# chariotgauge.net
KiCad netlist of a schematic drawn in EAGLE
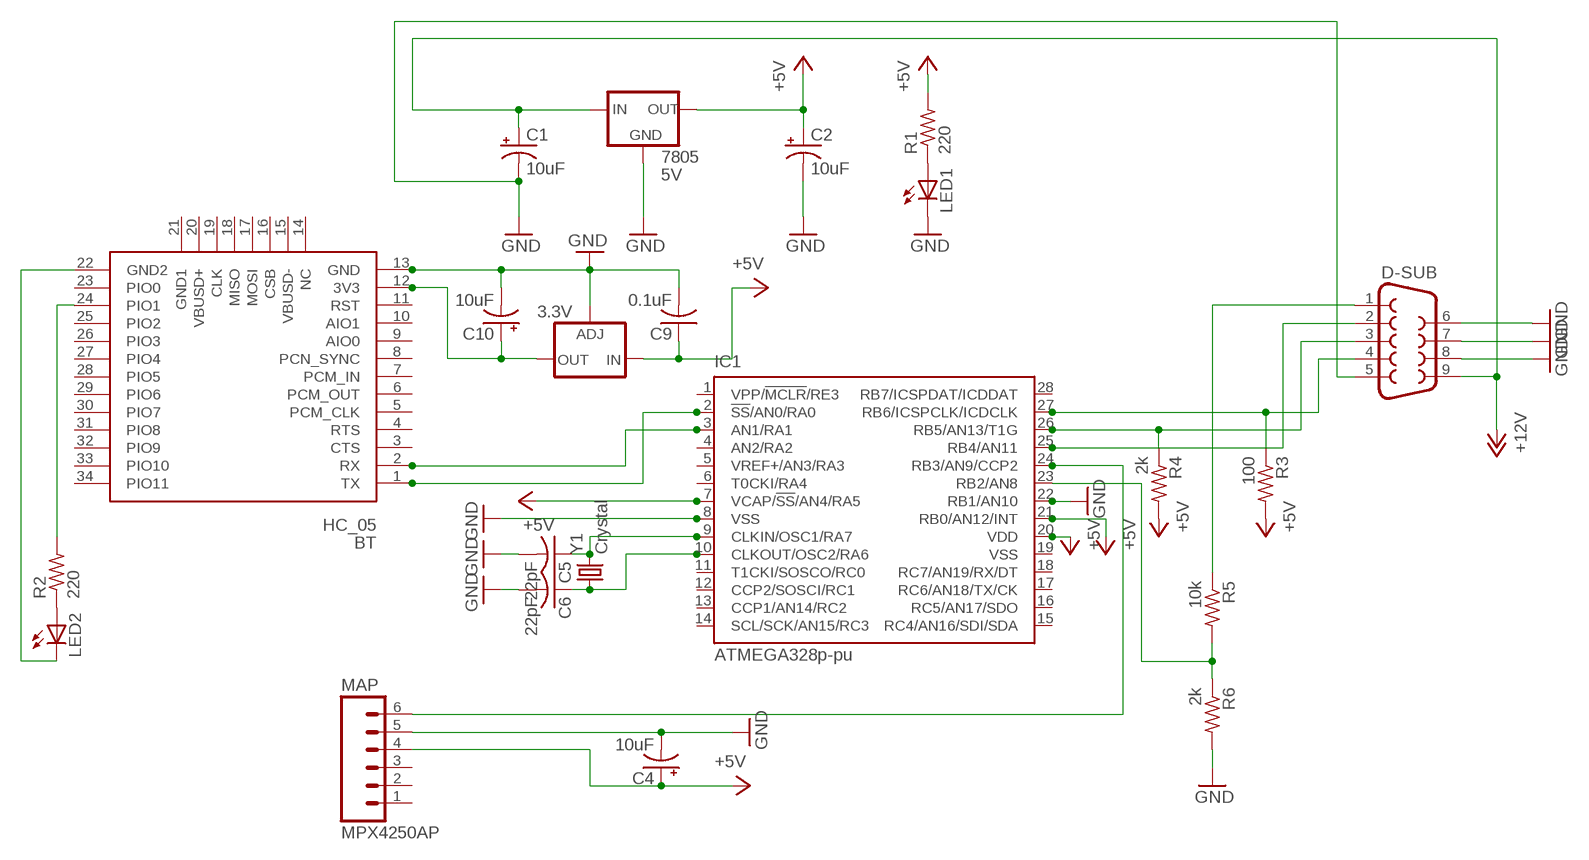
[diagram p0: schematic, sheet 1]

(export (version "E")
  (design (tool "Eeschema 10.0.6"))
  (components
    (comp (ref "3.3V")
      (value "LM317TL")
      (footprint "eagle-import:317TL")
      (libsource (lib "eagle-import") (part "LM317TL"))
    )
    (comp (ref "7805")
      (value "5V")
      (footprint "eagle-import:78XXL")
      (libsource (lib "eagle-import") (part "78XXL"))
    )
    (comp (ref "BT")
      (value "HC_05")
      (footprint "eagle-import:BLUETOOTH_SMD")
      (libsource (lib "eagle-import") (part "HC_05"))
    )
    (comp (ref "C1")
      (value "10uF")
      (footprint "eagle-import:CPOL-RADIAL-10UF-25V")
      (libsource (lib "eagle-import") (part "CAP_POLPTH2"))
    )
    (comp (ref "C2")
      (value "10uF")
      (footprint "eagle-import:CPOL-RADIAL-10UF-25V")
      (libsource (lib "eagle-import") (part "CAP_POLPTH2"))
    )
    (comp (ref "C4")
      (value "10uF")
      (footprint "eagle-import:CPOL-RADIAL-10UF-25V")
      (libsource (lib "eagle-import") (part "CAP_POLPTH2"))
    )
    (comp (ref "C5")
      (value "22pF")
      (footprint "eagle-import:C025-025X050")
      (libsource (lib "eagle-import") (part "C-US025-025X050"))
    )
    (comp (ref "C6")
      (value "22pF")
      (footprint "eagle-import:C025-025X050")
      (libsource (lib "eagle-import") (part "C-US025-025X050"))
    )
    (comp (ref "C9")
      (value "0.1uF")
      (footprint "eagle-import:C025-025X050")
      (libsource (lib "eagle-import") (part "C-US025-025X050"))
    )
    (comp (ref "C10")
      (value "10uF")
      (footprint "eagle-import:CPOL-RADIAL-10UF-25V")
      (libsource (lib "eagle-import") (part "CAP_POLPTH2"))
    )
    (comp (ref "D-SUB")
      (value "DB9FEMALE")
      (footprint "eagle-import:DB9")
      (libsource (lib "eagle-import") (part "DB9FEMALE"))
    )
    (comp (ref "IC1")
      (value "ATMEGA328p-pu")
      (footprint "eagle-import:DIL28-3")
      (libsource (lib "eagle-import") (part "PIC16F1516/18P"))
    )
    (comp (ref "LED1")
      (value "LED5MM")
      (footprint "eagle-import:LED5MM")
      (libsource (lib "eagle-import") (part "LED5MM"))
    )
    (comp (ref "LED2")
      (value "LED5MM")
      (footprint "eagle-import:LED5MM")
      (libsource (lib "eagle-import") (part "LED5MM"))
    )
    (comp (ref "MAP")
      (value "MPX4250AP")
      (footprint "eagle-import:1X06_LONGPADS")
      (libsource (lib "eagle-import") (part "M06LONGPADS"))
    )
    (comp (ref "R1")
      (value "220")
      (footprint "eagle-import:0204_7")
      (libsource (lib "eagle-import") (part "R-US_0204/7"))
    )
    (comp (ref "R2")
      (value "220")
      (footprint "eagle-import:0204_7")
      (libsource (lib "eagle-import") (part "R-US_0204/7"))
    )
    (comp (ref "R3")
      (value "100")
      (footprint "eagle-import:0204_7")
      (libsource (lib "eagle-import") (part "R-US_0204/7"))
    )
    (comp (ref "R4")
      (value "2k")
      (footprint "eagle-import:0204_7")
      (libsource (lib "eagle-import") (part "R-US_0204/7"))
    )
    (comp (ref "R5")
      (value "10k")
      (footprint "eagle-import:0204_7")
      (libsource (lib "eagle-import") (part "R-US_0204/7"))
    )
    (comp (ref "R6")
      (value "2k")
      (footprint "eagle-import:0204_7")
      (libsource (lib "eagle-import") (part "R-US_0204/7"))
    )
    (comp (ref "Y1")
      (value "Crystal")
      (footprint "eagle-import:HC49US")
      (libsource (lib "eagle-import") (part "CRYSTALHC49US"))
    )
  )
  (nets
    (net (code "1") (name "+5V") (class "Default")
      (node (ref "3.3V") (pin "3") (pinfunction "IN_3") (pintype "input"))
      (node (ref "7805") (pin "OUT") (pinfunction "OUT_OUT") (pintype "passive"))
      (node (ref "C2") (pin "1") (pinfunction "+_1") (pintype "passive"))
      (node (ref "C4") (pin "1") (pinfunction "+_1") (pintype "passive"))
      (node (ref "C9") (pin "1") (pinfunction "1_1") (pintype "passive"))
      (node (ref "IC1") (pin "20") (pinfunction "VDD_20") (pintype "power_in"))
      (node (ref "IC1") (pin "21") (pinfunction "RB0/AN12/INT_21") (pintype "bidirectional"))
      (node (ref "IC1") (pin "7") (pinfunction "VCAP/~{SS}/AN4/RA5_7") (pintype "bidirectional"))
      (node (ref "MAP") (pin "4") (pinfunction "4_4") (pintype "passive"))
      (node (ref "R1") (pin "2") (pinfunction "2_2") (pintype "passive"))
      (node (ref "R3") (pin "2") (pinfunction "2_2") (pintype "passive"))
      (node (ref "R4") (pin "2") (pinfunction "2_2") (pintype "passive"))
    )
    (net (code "2") (name "+12V") (class "Default")
      (node (ref "7805") (pin "IN") (pinfunction "IN_IN") (pintype "input"))
      (node (ref "C1") (pin "1") (pinfunction "+_1") (pintype "passive"))
      (node (ref "D-SUB") (pin "9") (pinfunction "9_9") (pintype "passive"))
    )
    (net (code "3") (name "/VSS") (class "Default")
      (node (ref "IC1") (pin "19") (pinfunction "VSS_19") (pintype "power_in"))
    )
    (net (code "4") (name "GND") (class "Default")
      (node (ref "3.3V") (pin "1") (pinfunction "ADJ_1") (pintype "input"))
      (node (ref "7805") (pin "GND") (pinfunction "GND_GND") (pintype "input"))
      (node (ref "BT") (pin "13") (pinfunction "GND_13") (pintype "bidirectional"))
      (node (ref "C1") (pin "2") (pinfunction "-_2") (pintype "passive"))
      (node (ref "C10") (pin "2") (pinfunction "-_2") (pintype "passive"))
      (node (ref "C2") (pin "2") (pinfunction "-_2") (pintype "passive"))
      (node (ref "C4") (pin "2") (pinfunction "-_2") (pintype "passive"))
      (node (ref "C5") (pin "2") (pinfunction "2_2") (pintype "passive"))
      (node (ref "C6") (pin "2") (pinfunction "2_2") (pintype "passive"))
      (node (ref "C9") (pin "2") (pinfunction "2_2") (pintype "passive"))
      (node (ref "D-SUB") (pin "5") (pinfunction "5_5") (pintype "passive"))
      (node (ref "D-SUB") (pin "6") (pinfunction "6_6") (pintype "passive"))
      (node (ref "D-SUB") (pin "7") (pinfunction "7_7") (pintype "passive"))
      (node (ref "D-SUB") (pin "8") (pinfunction "8_8") (pintype "passive"))
      (node (ref "IC1") (pin "22") (pinfunction "RB1/AN10_22") (pintype "bidirectional"))
      (node (ref "IC1") (pin "8") (pinfunction "VSS_8") (pintype "power_in"))
      (node (ref "LED1") (pin "K") (pinfunction "C_K") (pintype "passive"))
      (node (ref "MAP") (pin "5") (pinfunction "5_5") (pintype "passive"))
      (node (ref "R6") (pin "2") (pinfunction "2_2") (pintype "passive"))
    )
    (net (code "5") (name "Net-(3.3V-OUT)") (class "Default")
      (node (ref "3.3V") (pin "2") (pinfunction "OUT_2") (pintype "passive"))
      (node (ref "BT") (pin "12") (pinfunction "3V3_12") (pintype "bidirectional"))
      (node (ref "C10") (pin "1") (pinfunction "+_1") (pintype "passive"))
    )
    (net (code "6") (name "Net-(BT-GND2)") (class "Default")
      (node (ref "BT") (pin "22") (pinfunction "GND2_22") (pintype "bidirectional"))
      (node (ref "LED2") (pin "K") (pinfunction "C_K") (pintype "passive"))
    )
    (net (code "7") (name "Net-(BT-PIO1)") (class "Default")
      (node (ref "BT") (pin "24") (pinfunction "PIO1_24") (pintype "bidirectional"))
      (node (ref "R2") (pin "2") (pinfunction "2_2") (pintype "passive"))
    )
    (net (code "8") (name "Net-(BT-RX)") (class "Default")
      (node (ref "BT") (pin "2") (pinfunction "RX_2") (pintype "bidirectional"))
      (node (ref "IC1") (pin "3") (pinfunction "AN1/RA1_3") (pintype "bidirectional"))
    )
    (net (code "9") (name "Net-(BT-TX)") (class "Default")
      (node (ref "BT") (pin "1") (pinfunction "TX_1") (pintype "bidirectional"))
      (node (ref "IC1") (pin "2") (pinfunction "~{SS}/AN0/RA0_2") (pintype "bidirectional"))
    )
    (net (code "10") (name "Net-(D-SUB-Pad1)") (class "Default")
      (node (ref "D-SUB") (pin "1") (pinfunction "1_1") (pintype "passive"))
      (node (ref "R5") (pin "1") (pinfunction "1_1") (pintype "passive"))
    )
    (net (code "11") (name "Net-(IC1-CLKIN{slash}OSC1{slash}RA7)") (class "Default")
      (node (ref "C5") (pin "1") (pinfunction "1_1") (pintype "passive"))
      (node (ref "IC1") (pin "9") (pinfunction "CLKIN/OSC1/RA7_9") (pintype "bidirectional"))
      (node (ref "Y1") (pin "2") (pinfunction "2_2") (pintype "passive"))
    )
    (net (code "12") (name "Net-(IC1-CLKOUT{slash}OSC2{slash}RA6)") (class "Default")
      (node (ref "C6") (pin "1") (pinfunction "1_1") (pintype "passive"))
      (node (ref "IC1") (pin "10") (pinfunction "CLKOUT/OSC2/RA6_10") (pintype "bidirectional"))
      (node (ref "Y1") (pin "1") (pinfunction "1_1") (pintype "passive"))
    )
    (net (code "13") (name "Net-(IC1-RB2{slash}AN8)") (class "Default")
      (node (ref "IC1") (pin "23") (pinfunction "RB2/AN8_23") (pintype "bidirectional"))
      (node (ref "R5") (pin "2") (pinfunction "2_2") (pintype "passive"))
      (node (ref "R6") (pin "1") (pinfunction "1_1") (pintype "passive"))
    )
    (net (code "14") (name "Net-(IC1-RB3{slash}AN9{slash}CCP2)") (class "Default")
      (node (ref "IC1") (pin "24") (pinfunction "RB3/AN9/CCP2_24") (pintype "bidirectional"))
      (node (ref "MAP") (pin "6") (pinfunction "6_6") (pintype "passive"))
    )
    (net (code "15") (name "Net-(IC1-RB4{slash}AN11)") (class "Default")
      (node (ref "D-SUB") (pin "2") (pinfunction "2_2") (pintype "passive"))
      (node (ref "IC1") (pin "25") (pinfunction "RB4/AN11_25") (pintype "bidirectional"))
    )
    (net (code "16") (name "Net-(IC1-RB5{slash}AN13{slash}T1G)") (class "Default")
      (node (ref "D-SUB") (pin "3") (pinfunction "3_3") (pintype "passive"))
      (node (ref "IC1") (pin "26") (pinfunction "RB5/AN13/T1G_26") (pintype "bidirectional"))
      (node (ref "R4") (pin "1") (pinfunction "1_1") (pintype "passive"))
    )
    (net (code "17") (name "Net-(IC1-RB6{slash}ICSPCLK{slash}ICDCLK)") (class "Default")
      (node (ref "D-SUB") (pin "4") (pinfunction "4_4") (pintype "passive"))
      (node (ref "IC1") (pin "27") (pinfunction "RB6/ICSPCLK/ICDCLK_27") (pintype "bidirectional"))
      (node (ref "R3") (pin "1") (pinfunction "1_1") (pintype "passive"))
    )
    (net (code "18") (name "Net-(LED1-PadA)") (class "Default")
      (node (ref "LED1") (pin "A") (pinfunction "A_A") (pintype "passive"))
      (node (ref "R1") (pin "1") (pinfunction "1_1") (pintype "passive"))
    )
    (net (code "19") (name "Net-(LED2-PadA)") (class "Default")
      (node (ref "LED2") (pin "A") (pinfunction "A_A") (pintype "passive"))
      (node (ref "R2") (pin "1") (pinfunction "1_1") (pintype "passive"))
    )
    (net (code "20") (name "unconnected-(BT-AIO0-Pad9)") (class "Default")
      (node (ref "BT") (pin "9") (pinfunction "AIO0_9") (pintype "bidirectional"))
    )
    (net (code "21") (name "unconnected-(BT-AIO1-Pad10)") (class "Default")
      (node (ref "BT") (pin "10") (pinfunction "AIO1_10") (pintype "bidirectional"))
    )
    (net (code "22") (name "unconnected-(BT-CLK-Pad19)") (class "Default")
      (node (ref "BT") (pin "19") (pinfunction "CLK_19") (pintype "bidirectional"))
    )
    (net (code "23") (name "unconnected-(BT-CSB-Pad16)") (class "Default")
      (node (ref "BT") (pin "16") (pinfunction "CSB_16") (pintype "bidirectional"))
    )
    (net (code "24") (name "unconnected-(BT-CTS-Pad3)") (class "Default")
      (node (ref "BT") (pin "3") (pinfunction "CTS_3") (pintype "bidirectional"))
    )
    (net (code "25") (name "unconnected-(BT-GND1-Pad21)") (class "Default")
      (node (ref "BT") (pin "21") (pinfunction "GND1_21") (pintype "bidirectional"))
    )
    (net (code "26") (name "unconnected-(BT-MISO-Pad18)") (class "Default")
      (node (ref "BT") (pin "18") (pinfunction "MISO_18") (pintype "bidirectional"))
    )
    (net (code "27") (name "unconnected-(BT-MOSI-Pad17)") (class "Default")
      (node (ref "BT") (pin "17") (pinfunction "MOSI_17") (pintype "bidirectional"))
    )
    (net (code "28") (name "unconnected-(BT-NC-Pad14)") (class "Default")
      (node (ref "BT") (pin "14") (pinfunction "NC_14") (pintype "bidirectional"))
    )
    (net (code "29") (name "unconnected-(BT-PCM_CLK-Pad5)") (class "Default")
      (node (ref "BT") (pin "5") (pinfunction "PCM_CLK_5") (pintype "bidirectional"))
    )
    (net (code "30") (name "unconnected-(BT-PCM_IN-Pad7)") (class "Default")
      (node (ref "BT") (pin "7") (pinfunction "PCM_IN_7") (pintype "bidirectional"))
    )
    (net (code "31") (name "unconnected-(BT-PCM_OUT-Pad6)") (class "Default")
      (node (ref "BT") (pin "6") (pinfunction "PCM_OUT_6") (pintype "bidirectional"))
    )
    (net (code "32") (name "unconnected-(BT-PCN_SYNC-Pad8)") (class "Default")
      (node (ref "BT") (pin "8") (pinfunction "PCN_SYNC_8") (pintype "bidirectional"))
    )
    (net (code "33") (name "unconnected-(BT-PIO0-Pad23)") (class "Default")
      (node (ref "BT") (pin "23") (pinfunction "PIO0_23") (pintype "bidirectional"))
    )
    (net (code "34") (name "unconnected-(BT-PIO2-Pad25)") (class "Default")
      (node (ref "BT") (pin "25") (pinfunction "PIO2_25") (pintype "bidirectional"))
    )
    (net (code "35") (name "unconnected-(BT-PIO3-Pad26)") (class "Default")
      (node (ref "BT") (pin "26") (pinfunction "PIO3_26") (pintype "bidirectional"))
    )
    (net (code "36") (name "unconnected-(BT-PIO4-Pad27)") (class "Default")
      (node (ref "BT") (pin "27") (pinfunction "PIO4_27") (pintype "bidirectional"))
    )
    (net (code "37") (name "unconnected-(BT-PIO5-Pad28)") (class "Default")
      (node (ref "BT") (pin "28") (pinfunction "PIO5_28") (pintype "bidirectional"))
    )
    (net (code "38") (name "unconnected-(BT-PIO6-Pad29)") (class "Default")
      (node (ref "BT") (pin "29") (pinfunction "PIO6_29") (pintype "bidirectional"))
    )
    (net (code "39") (name "unconnected-(BT-PIO7-Pad30)") (class "Default")
      (node (ref "BT") (pin "30") (pinfunction "PIO7_30") (pintype "bidirectional"))
    )
    (net (code "40") (name "unconnected-(BT-PIO8-Pad31)") (class "Default")
      (node (ref "BT") (pin "31") (pinfunction "PIO8_31") (pintype "bidirectional"))
    )
    (net (code "41") (name "unconnected-(BT-PIO9-Pad32)") (class "Default")
      (node (ref "BT") (pin "32") (pinfunction "PIO9_32") (pintype "bidirectional"))
    )
    (net (code "42") (name "unconnected-(BT-PIO10-Pad33)") (class "Default")
      (node (ref "BT") (pin "33") (pinfunction "PIO10_33") (pintype "bidirectional"))
    )
    (net (code "43") (name "unconnected-(BT-PIO11-Pad34)") (class "Default")
      (node (ref "BT") (pin "34") (pinfunction "PIO11_34") (pintype "bidirectional"))
    )
    (net (code "44") (name "unconnected-(BT-RST-Pad11)") (class "Default")
      (node (ref "BT") (pin "11") (pinfunction "RST_11") (pintype "bidirectional"))
    )
    (net (code "45") (name "unconnected-(BT-RTS-Pad4)") (class "Default")
      (node (ref "BT") (pin "4") (pinfunction "RTS_4") (pintype "bidirectional"))
    )
    (net (code "46") (name "unconnected-(BT-VBUSD+-Pad20)") (class "Default")
      (node (ref "BT") (pin "20") (pinfunction "VBUSD+_20") (pintype "bidirectional"))
    )
    (net (code "47") (name "unconnected-(BT-VBUSD--Pad15)") (class "Default")
      (node (ref "BT") (pin "15") (pinfunction "VBUSD-_15") (pintype "bidirectional"))
    )
    (net (code "48") (name "unconnected-(IC1-AN2{slash}RA2-Pad4)") (class "Default")
      (node (ref "IC1") (pin "4") (pinfunction "AN2/RA2_4") (pintype "bidirectional"))
    )
    (net (code "49") (name "unconnected-(IC1-CCP1{slash}AN14{slash}RC2-Pad13)") (class "Default")
      (node (ref "IC1") (pin "13") (pinfunction "CCP1/AN14/RC2_13") (pintype "bidirectional"))
    )
    (net (code "50") (name "unconnected-(IC1-CCP2{slash}SOSCI{slash}RC1-Pad12)") (class "Default")
      (node (ref "IC1") (pin "12") (pinfunction "CCP2/SOSCI/RC1_12") (pintype "bidirectional"))
    )
    (net (code "51") (name "unconnected-(IC1-RB7{slash}ICSPDAT{slash}ICDDAT-Pad28)") (class "Default")
      (node (ref "IC1") (pin "28") (pinfunction "RB7/ICSPDAT/ICDDAT_28") (pintype "bidirectional"))
    )
    (net (code "52") (name "unconnected-(IC1-RC4{slash}AN16{slash}SDI{slash}SDA-Pad15)") (class "Default")
      (node (ref "IC1") (pin "15") (pinfunction "RC4/AN16/SDI/SDA_15") (pintype "bidirectional"))
    )
    (net (code "53") (name "unconnected-(IC1-RC5{slash}AN17{slash}SDO-Pad16)") (class "Default")
      (node (ref "IC1") (pin "16") (pinfunction "RC5/AN17/SDO_16") (pintype "bidirectional"))
    )
    (net (code "54") (name "unconnected-(IC1-RC6{slash}AN18{slash}TX{slash}CK-Pad17)") (class "Default")
      (node (ref "IC1") (pin "17") (pinfunction "RC6/AN18/TX/CK_17") (pintype "bidirectional"))
    )
    (net (code "55") (name "unconnected-(IC1-RC7{slash}AN19{slash}RX{slash}DT-Pad18)") (class "Default")
      (node (ref "IC1") (pin "18") (pinfunction "RC7/AN19/RX/DT_18") (pintype "bidirectional"))
    )
    (net (code "56") (name "unconnected-(IC1-SCL{slash}SCK{slash}AN15{slash}RC3-Pad14)") (class "Default")
      (node (ref "IC1") (pin "14") (pinfunction "SCL/SCK/AN15/RC3_14") (pintype "bidirectional"))
    )
    (net (code "57") (name "unconnected-(IC1-T0CKI{slash}RA4-Pad6)") (class "Default")
      (node (ref "IC1") (pin "6") (pinfunction "T0CKI/RA4_6") (pintype "bidirectional"))
    )
    (net (code "58") (name "unconnected-(IC1-T1CKI{slash}SOSCO{slash}RC0-Pad11)") (class "Default")
      (node (ref "IC1") (pin "11") (pinfunction "T1CKI/SOSCO/RC0_11") (pintype "bidirectional"))
    )
    (net (code "59") (name "unconnected-(IC1-VPP{slash}~{MCLR}{slash}RE3-Pad1)") (class "Default")
      (node (ref "IC1") (pin "1") (pinfunction "VPP/~{MCLR}/RE3_1") (pintype "bidirectional"))
    )
    (net (code "60") (name "unconnected-(IC1-VREF+{slash}AN3{slash}RA3-Pad5)") (class "Default")
      (node (ref "IC1") (pin "5") (pinfunction "VREF+/AN3/RA3_5") (pintype "bidirectional"))
    )
    (net (code "61") (name "unconnected-(MAP-Pad1)") (class "Default")
      (node (ref "MAP") (pin "1") (pinfunction "1_1") (pintype "passive"))
    )
    (net (code "62") (name "unconnected-(MAP-Pad2)") (class "Default")
      (node (ref "MAP") (pin "2") (pinfunction "2_2") (pintype "passive"))
    )
    (net (code "63") (name "unconnected-(MAP-Pad3)") (class "Default")
      (node (ref "MAP") (pin "3") (pinfunction "3_3") (pintype "passive"))
    )
  )
)
